# AMS1117_breakout.net
KiCad netlist of a schematic drawn in Altium Designer
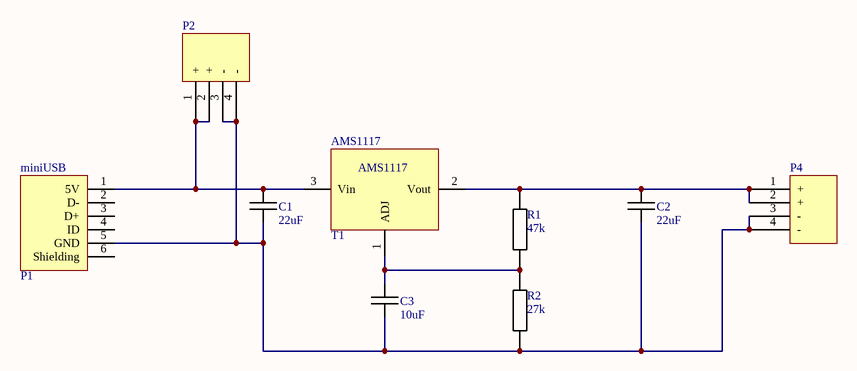
[diagram p0: AMS1117 breakout.SchDoc]

(export (version "E")
  (design (tool "Eeschema 10.0.6"))
  (components
    (comp (ref "AMS1117")
      (value "T1")
      (footprint "SOT-223")
      (libsource (lib "AMS1117 breakout") (part "AMS1117"))
    )
    (comp (ref "C1")
      (value "22uF")
      (footprint "0805-C")
      (libsource (lib "AMS1117 breakout") (part "Capacitor"))
    )
    (comp (ref "C2")
      (value "22uF")
      (footprint "0805-C")
      (libsource (lib "AMS1117 breakout") (part "Capacitor"))
    )
    (comp (ref "C3")
      (value "10uF")
      (footprint "0805-C")
      (libsource (lib "AMS1117 breakout") (part "Capacitor"))
    )
    (comp (ref "miniUSB") (value "P1") (libsource (lib "AMS1117 breakout") (part "miniUSB")))
    (comp (ref "P2") (value "Header 4pin") (libsource (lib "AMS1117 breakout") (part "Header 4pin")))
    (comp (ref "P4") (value "Header 4pin") (libsource (lib "") (part "Header 4pin_1")))
    (comp (ref "R1")
      (value "47k")
      (footprint "0805-R")
      (libsource (lib "AMS1117 breakout") (part "Resistor"))
    )
    (comp (ref "R2")
      (value "27k")
      (footprint "0805-R")
      (libsource (lib "AMS1117 breakout") (part "Resistor"))
    )
  )
  (nets
    (net (code "1") (name "Net-(AMS1117-ADJ)") (class "Default")
      (node (ref "AMS1117") (pin "1") (pinfunction "ADJ_1") (pintype "passive"))
      (node (ref "C3") (pin "2") (pinfunction "2_2") (pintype "passive"))
      (node (ref "R1") (pin "1") (pinfunction "1_1") (pintype "passive"))
      (node (ref "R2") (pin "2") (pinfunction "2_2") (pintype "passive"))
    )
    (net (code "2") (name "Net-(AMS1117-Vin)") (class "Default")
      (node (ref "AMS1117") (pin "3") (pinfunction "Vin_3") (pintype "passive"))
      (node (ref "C1") (pin "2") (pinfunction "2_2") (pintype "passive"))
      (node (ref "P2") (pin "1") (pinfunction "+_1") (pintype "passive"))
      (node (ref "P2") (pin "2") (pinfunction "+_2") (pintype "passive"))
      (node (ref "miniUSB") (pin "1") (pinfunction "5V_1") (pintype "passive"))
    )
    (net (code "3") (name "Net-(AMS1117-Vout)") (class "Default")
      (node (ref "AMS1117") (pin "2") (pinfunction "Vout_2") (pintype "passive"))
      (node (ref "C2") (pin "2") (pinfunction "2_2") (pintype "passive"))
      (node (ref "P4") (pin "1") (pinfunction "+_1") (pintype "passive"))
      (node (ref "P4") (pin "2") (pinfunction "+_2") (pintype "passive"))
      (node (ref "R1") (pin "2") (pinfunction "2_2") (pintype "passive"))
    )
    (net (code "4") (name "Net-(miniUSB-GND)") (class "Default")
      (node (ref "C1") (pin "1") (pinfunction "1_1") (pintype "passive"))
      (node (ref "C2") (pin "1") (pinfunction "1_1") (pintype "passive"))
      (node (ref "C3") (pin "1") (pinfunction "1_1") (pintype "passive"))
      (node (ref "P2") (pin "3") (pinfunction "-_3") (pintype "passive"))
      (node (ref "P2") (pin "4") (pinfunction "-_4") (pintype "passive"))
      (node (ref "P4") (pin "3") (pinfunction "-_3") (pintype "passive"))
      (node (ref "P4") (pin "4") (pinfunction "-_4") (pintype "passive"))
      (node (ref "R2") (pin "1") (pinfunction "1_1") (pintype "passive"))
      (node (ref "miniUSB") (pin "5") (pinfunction "GND_5") (pintype "passive"))
    )
    (net (code "5") (name "unconnected-(miniUSB-D+-Pad3)") (class "Default")
      (node (ref "miniUSB") (pin "3") (pinfunction "D+_3") (pintype "passive"))
    )
    (net (code "6") (name "unconnected-(miniUSB-D--Pad2)") (class "Default")
      (node (ref "miniUSB") (pin "2") (pinfunction "D-_2") (pintype "passive"))
    )
    (net (code "7") (name "unconnected-(miniUSB-ID-Pad4)") (class "Default")
      (node (ref "miniUSB") (pin "4") (pinfunction "ID_4") (pintype "passive"))
    )
    (net (code "8") (name "unconnected-(miniUSB-Shielding-Pad6)") (class "Default")
      (node (ref "miniUSB") (pin "6") (pinfunction "Shielding_6") (pintype "passive"))
    )
  )
)
